# uart.net
KiCad netlist of a schematic drawn in Altium Designer
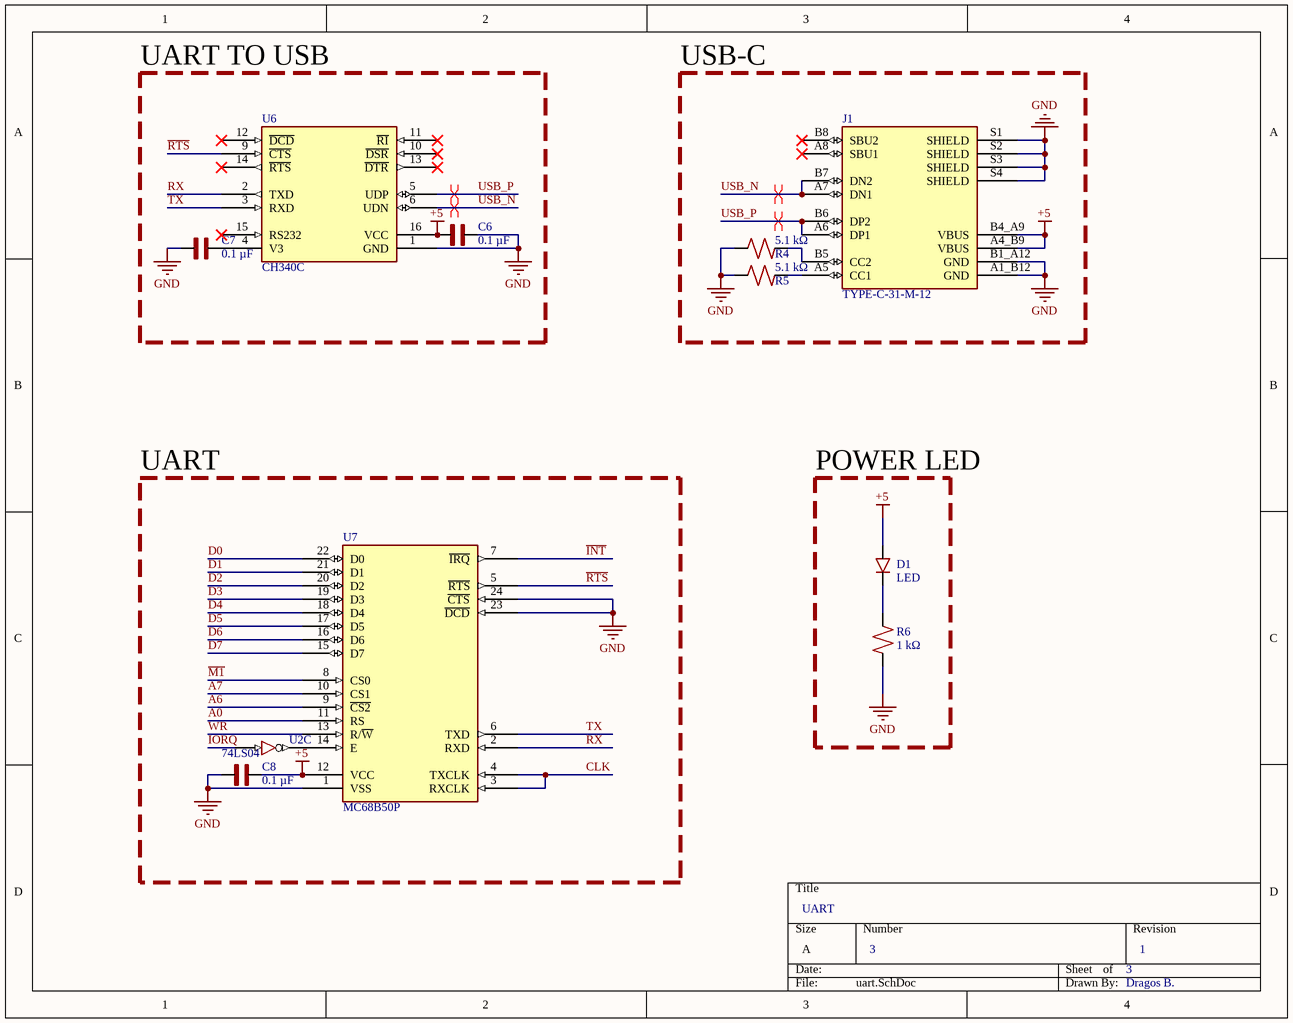
[diagram p0: uart.SchDoc]

(export (version "E")
  (design (tool "Eeschema 10.0.6"))
  (components
    (comp (ref "C6")
      (value "0.1 µF")
      (footprint "Capacitor")
      (fields (field (name "MP") "ECWFG70105K") (field (name "MF") "Panasonic"))
      (libsource (lib "components") (part "CAPACITOR"))
    )
    (comp (ref "C7")
      (value "0.1 µF")
      (footprint "Capacitor")
      (fields (field (name "MP") "ECWFG70105K") (field (name "MF") "Panasonic"))
      (libsource (lib "components") (part "CAPACITOR"))
    )
    (comp (ref "C8")
      (value "0.1 µF")
      (footprint "Capacitor")
      (fields (field (name "MP") "ECWFG70105K") (field (name "MF") "Panasonic"))
      (libsource (lib "components") (part "CAPACITOR"))
    )
    (comp (ref "D1") (value "LED") (footprint "DIODE") (libsource (lib "components") (part "LED")))
    (comp (ref "J1")
      (value "TYPE-C-31-M-12")
      (footprint "HRO_TYPE-C-31-M-12")
      (fields (field (name "MF") "HRO Electronics Co., Ltd."))
      (libsource (lib "components") (part "TYPE-C-31-M-12"))
    )
    (comp (ref "R4")
      (value "5.1 kΩ")
      (footprint "Axial 0.4")
      (fields (field (name "MP") "ERJU01J131C"))
      (libsource (lib "components") (part "RESISTOR"))
    )
    (comp (ref "R5")
      (value "5.1 kΩ")
      (footprint "Axial 0.4")
      (fields (field (name "MP") "ERJU01J131C"))
      (libsource (lib "components") (part "RESISTOR"))
    )
    (comp (ref "R6")
      (value "1 kΩ")
      (footprint "Axial 0.4")
      (fields (field (name "MP") "ERJU01J131C"))
      (libsource (lib "components") (part "RESISTOR"))
    )
    (comp (ref "U2")
      (value "74LS04")
      (footprint "DIP14")
      (description "Hex Inverters")
      (libsource (lib "components") (part "74LS04"))
    )
    (comp (ref "U6")
      (value "CH340C")
      (footprint "SOP127P600X175-16M")
      (libsource (lib "components") (part "CH340C"))
    )
    (comp (ref "U7") (value "MC68B50P") (footprint "DIP24") (libsource (lib "components") (part "MC68B50P")))
  )
  (nets
    (net (code "1") (name "+5") (class "Default")
      (node (ref "C6") (pin "2") (pinfunction "2_2") (pintype "passive"))
      (node (ref "C8") (pin "1") (pinfunction "1_1") (pintype "passive"))
      (node (ref "D1") (pin "A") (pinfunction "A_A") (pintype "passive"))
      (node (ref "J1") (pin "A4_B9") (pinfunction "VBUS_A4_B9") (pintype "power_in"))
      (node (ref "J1") (pin "B4_A9") (pinfunction "VBUS_B4_A9") (pintype "power_in"))
      (node (ref "U6") (pin "16") (pinfunction "VCC_16") (pintype "power_in"))
      (node (ref "U7") (pin "12") (pinfunction "VCC_12") (pintype "power_in"))
    )
    (net (code "2") (name "/A0") (class "Default")
      (node (ref "U7") (pin "11") (pinfunction "RS_11") (pintype "input"))
    )
    (net (code "3") (name "/A6") (class "Default")
      (node (ref "U7") (pin "9") (pinfunction "CS2_9") (pintype "input"))
    )
    (net (code "4") (name "/A7") (class "Default")
      (node (ref "U7") (pin "10") (pinfunction "CS1_10") (pintype "input"))
    )
    (net (code "5") (name "/CLK") (class "Default")
      (node (ref "U7") (pin "3") (pinfunction "RXCLK_3") (pintype "input"))
      (node (ref "U7") (pin "4") (pinfunction "TXCLK_4") (pintype "input"))
    )
    (net (code "6") (name "/D0") (class "Default")
      (node (ref "U7") (pin "22") (pinfunction "D0_22") (pintype "bidirectional"))
    )
    (net (code "7") (name "/D1") (class "Default")
      (node (ref "U7") (pin "21") (pinfunction "D1_21") (pintype "bidirectional"))
    )
    (net (code "8") (name "/D2") (class "Default")
      (node (ref "U7") (pin "20") (pinfunction "D2_20") (pintype "bidirectional"))
    )
    (net (code "9") (name "/D3") (class "Default")
      (node (ref "U7") (pin "19") (pinfunction "D3_19") (pintype "bidirectional"))
    )
    (net (code "10") (name "/D4") (class "Default")
      (node (ref "U7") (pin "18") (pinfunction "D4_18") (pintype "bidirectional"))
    )
    (net (code "11") (name "/D5") (class "Default")
      (node (ref "U7") (pin "17") (pinfunction "D5_17") (pintype "bidirectional"))
    )
    (net (code "12") (name "/D6") (class "Default")
      (node (ref "U7") (pin "16") (pinfunction "D6_16") (pintype "bidirectional"))
    )
    (net (code "13") (name "/D7") (class "Default")
      (node (ref "U7") (pin "15") (pinfunction "D7_15") (pintype "bidirectional"))
    )
    (net (code "14") (name "/INT") (class "Default")
      (node (ref "U7") (pin "7") (pinfunction "IRQ_7") (pintype "output"))
    )
    (net (code "15") (name "/IORQ") (class "Default")
      (node (ref "U2") (pin "5") (pinfunction "A3_5") (pintype "input"))
    )
    (net (code "16") (name "/M1") (class "Default")
      (node (ref "U7") (pin "8") (pinfunction "CS0_8") (pintype "input"))
    )
    (net (code "17") (name "/RTS") (class "Default")
      (node (ref "U6") (pin "9") (pinfunction "CTS_9") (pintype "input"))
      (node (ref "U7") (pin "5") (pinfunction "RTS_5") (pintype "output"))
    )
    (net (code "18") (name "/RX") (class "Default")
      (node (ref "U6") (pin "2") (pinfunction "TXD_2") (pintype "output"))
      (node (ref "U7") (pin "2") (pinfunction "RXD_2") (pintype "input"))
    )
    (net (code "19") (name "/TX") (class "Default")
      (node (ref "U6") (pin "3") (pinfunction "RXD_3") (pintype "input"))
      (node (ref "U7") (pin "6") (pinfunction "TXD_6") (pintype "output"))
    )
    (net (code "20") (name "/USB_N") (class "Default")
      (node (ref "J1") (pin "A7") (pinfunction "DN1_A7") (pintype "bidirectional"))
      (node (ref "J1") (pin "B7") (pinfunction "DN2_B7") (pintype "bidirectional"))
      (node (ref "U6") (pin "6") (pinfunction "UDN_6") (pintype "bidirectional"))
    )
    (net (code "21") (name "/USB_P") (class "Default")
      (node (ref "J1") (pin "A6") (pinfunction "DP1_A6") (pintype "bidirectional"))
      (node (ref "J1") (pin "B6") (pinfunction "DP2_B6") (pintype "bidirectional"))
      (node (ref "U6") (pin "5") (pinfunction "UDP_5") (pintype "bidirectional"))
    )
    (net (code "22") (name "/WR") (class "Default")
      (node (ref "U7") (pin "13") (pinfunction "R/~{W}_13") (pintype "input"))
    )
    (net (code "23") (name "GND") (class "Default")
      (node (ref "C6") (pin "1") (pinfunction "1_1") (pintype "passive"))
      (node (ref "C7") (pin "2") (pinfunction "2_2") (pintype "passive"))
      (node (ref "C8") (pin "2") (pinfunction "2_2") (pintype "passive"))
      (node (ref "J1") (pin "A1_B12") (pinfunction "GND_A1_B12") (pintype "power_in"))
      (node (ref "J1") (pin "B1_A12") (pinfunction "GND_B1_A12") (pintype "power_in"))
      (node (ref "J1") (pin "S1") (pinfunction "SHIELD_S1") (pintype "passive"))
      (node (ref "J1") (pin "S2") (pinfunction "SHIELD_S2") (pintype "passive"))
      (node (ref "J1") (pin "S3") (pinfunction "SHIELD_S3") (pintype "passive"))
      (node (ref "J1") (pin "S4") (pinfunction "SHIELD_S4") (pintype "passive"))
      (node (ref "R4") (pin "1") (pinfunction "1_1") (pintype "passive"))
      (node (ref "R5") (pin "1") (pinfunction "1_1") (pintype "passive"))
      (node (ref "R6") (pin "1") (pinfunction "1_1") (pintype "passive"))
      (node (ref "U6") (pin "1") (pinfunction "GND_1") (pintype "power_in"))
      (node (ref "U7") (pin "1") (pinfunction "VSS_1") (pintype "power_in"))
      (node (ref "U7") (pin "23") (pinfunction "DCD_23") (pintype "input"))
      (node (ref "U7") (pin "24") (pinfunction "CTS_24") (pintype "input"))
    )
    (net (code "24") (name "Net-(D1-PadK)") (class "Default")
      (node (ref "D1") (pin "K") (pinfunction "K_K") (pintype "passive"))
      (node (ref "R6") (pin "2") (pinfunction "2_2") (pintype "passive"))
    )
    (net (code "25") (name "Net-(J1-CC1)") (class "Default")
      (node (ref "J1") (pin "A5") (pinfunction "CC1_A5") (pintype "bidirectional"))
      (node (ref "R5") (pin "2") (pinfunction "2_2") (pintype "passive"))
    )
    (net (code "26") (name "Net-(J1-CC2)") (class "Default")
      (node (ref "J1") (pin "B5") (pinfunction "CC2_B5") (pintype "bidirectional"))
      (node (ref "R4") (pin "2") (pinfunction "2_2") (pintype "passive"))
    )
    (net (code "27") (name "Net-(U2C-Y3)") (class "Default")
      (node (ref "U2") (pin "6") (pinfunction "Y3_6") (pintype "output"))
      (node (ref "U7") (pin "14") (pinfunction "E_14") (pintype "input"))
    )
    (net (code "28") (name "Net-(U6-V3)") (class "Default")
      (node (ref "C7") (pin "1") (pinfunction "1_1") (pintype "passive"))
      (node (ref "U6") (pin "4") (pinfunction "V3_4") (pintype "power_in"))
    )
    (net (code "29") (name "unconnected-(J1-SBU1-PadA8)") (class "Default")
      (node (ref "J1") (pin "A8") (pinfunction "SBU1_A8") (pintype "bidirectional+no_connect"))
    )
    (net (code "30") (name "unconnected-(J1-SBU2-PadB8)") (class "Default")
      (node (ref "J1") (pin "B8") (pinfunction "SBU2_B8") (pintype "bidirectional+no_connect"))
    )
    (net (code "31") (name "unconnected-(U6-DCD-Pad12)") (class "Default")
      (node (ref "U6") (pin "12") (pinfunction "DCD_12") (pintype "input+no_connect"))
    )
    (net (code "32") (name "unconnected-(U6-DSR-Pad10)") (class "Default")
      (node (ref "U6") (pin "10") (pinfunction "DSR_10") (pintype "input+no_connect"))
    )
    (net (code "33") (name "unconnected-(U6-DTR-Pad13)") (class "Default")
      (node (ref "U6") (pin "13") (pinfunction "DTR_13") (pintype "output+no_connect"))
    )
    (net (code "34") (name "unconnected-(U6-RI-Pad11)") (class "Default")
      (node (ref "U6") (pin "11") (pinfunction "RI_11") (pintype "input+no_connect"))
    )
    (net (code "35") (name "unconnected-(U6-RS232-Pad15)") (class "Default")
      (node (ref "U6") (pin "15") (pinfunction "RS232_15") (pintype "input+no_connect"))
    )
    (net (code "36") (name "unconnected-(U6-RTS-Pad14)") (class "Default")
      (node (ref "U6") (pin "14") (pinfunction "RTS_14") (pintype "output+no_connect"))
    )
  )
)
